# basic_board.net
KiCad netlist of a schematic drawn in EAGLE
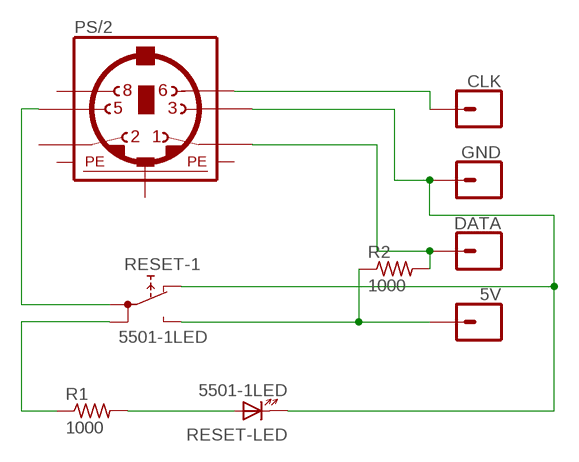
[diagram p0: schematic, sheet 1]

(export (version "E")
  (design (tool "Eeschema 10.0.6"))
  (components
    (comp (ref "5V")
      (value "CONN_01")
      (footprint "eagle-import:1X01")
      (libsource (lib "eagle-import") (part "CONN_01"))
    )
    (comp (ref "CLK")
      (value "CONN_01")
      (footprint "eagle-import:1X01")
      (libsource (lib "eagle-import") (part "CONN_01"))
    )
    (comp (ref "DATA")
      (value "CONN_01")
      (footprint "eagle-import:1X01")
      (libsource (lib "eagle-import") (part "CONN_01"))
    )
    (comp (ref "GND")
      (value "CONN_01")
      (footprint "eagle-import:1X01")
      (libsource (lib "eagle-import") (part "CONN_01"))
    )
    (comp (ref "PS/2")
      (value "MINI_DIN_6")
      (footprint "eagle-import:M_DIN6")
      (libsource (lib "eagle-import") (part "MINI_DIN_6"))
    )
    (comp (ref "R1")
      (value "1000")
      (footprint "eagle-import:0309_12")
      (libsource (lib "eagle-import") (part "R-US_0309/12"))
    )
    (comp (ref "R2")
      (value "1000")
      (footprint "eagle-import:0309_12")
      (libsource (lib "eagle-import") (part "R-US_0309/12"))
    )
    (comp (ref "RESET")
      (value "5501-1LED")
      (footprint "eagle-import:5501-1LED")
      (libsource (lib "eagle-import") (part "55?-1LED01"))
    )
  )
  (nets
    (net (code "1") (name "/PE1") (class "Default")
      (node (ref "PS/2") (pin "SH1") (pinfunction "PE1_SH1") (pintype "power_in"))
    )
    (net (code "2") (name "/PE2") (class "Default")
      (node (ref "PS/2") (pin "SH2") (pinfunction "PE2_SH2") (pintype "power_in"))
    )
    (net (code "3") (name "/PE3") (class "Default")
      (node (ref "PS/2") (pin "SH3") (pinfunction "PE3_SH3") (pintype "power_in"))
    )
    (net (code "4") (name "Net-(5V-Pad1)") (class "Default")
      (node (ref "5V") (pin "1") (pinfunction "1_1") (pintype "passive"))
      (node (ref "R2") (pin "1") (pinfunction "1_1") (pintype "passive"))
      (node (ref "RESET") (pin "NO") (pinfunction "NO_NO") (pintype "passive"))
    )
    (net (code "5") (name "Net-(CLK-Pad1)") (class "Default")
      (node (ref "CLK") (pin "1") (pinfunction "1_1") (pintype "passive"))
      (node (ref "PS/2") (pin "6") (pinfunction "6_6") (pintype "passive"))
    )
    (net (code "6") (name "Net-(DATA-Pad1)") (class "Default")
      (node (ref "DATA") (pin "1") (pinfunction "1_1") (pintype "passive"))
      (node (ref "PS/2") (pin "1") (pinfunction "1_1") (pintype "passive"))
      (node (ref "R2") (pin "2") (pinfunction "2_2") (pintype "passive"))
    )
    (net (code "7") (name "Net-(PS/2-Pad5)") (class "Default")
      (node (ref "PS/2") (pin "5") (pinfunction "5_5") (pintype "passive"))
      (node (ref "RESET") (pin "1A") (pinfunction "1A_1A") (pintype "passive"))
    )
    (net (code "8") (name "Net-(R1-Pad1)") (class "Default")
      (node (ref "R1") (pin "1") (pinfunction "1_1") (pintype "passive"))
      (node (ref "RESET") (pin "1B") (pinfunction "1B_1B") (pintype "passive"))
    )
    (net (code "9") (name "Net-(RESETB-A)") (class "Default")
      (node (ref "R1") (pin "2") (pinfunction "2_2") (pintype "passive"))
      (node (ref "RESET") (pin "+") (pinfunction "A_+") (pintype "passive"))
    )
    (net (code "10") (name "Net-(RESETB-K)") (class "Default")
      (node (ref "GND") (pin "1") (pinfunction "1_1") (pintype "passive"))
      (node (ref "PS/2") (pin "3") (pinfunction "3_3") (pintype "passive"))
      (node (ref "RESET") (pin "-") (pinfunction "K_-") (pintype "passive"))
      (node (ref "RESET") (pin "NC") (pinfunction "NC_NC") (pintype "passive"))
    )
    (net (code "11") (name "unconnected-(PS/2-Pad2)") (class "Default")
      (node (ref "PS/2") (pin "2") (pinfunction "2_2") (pintype "passive"))
    )
    (net (code "12") (name "unconnected-(PS/2-Pad8)") (class "Default")
      (node (ref "PS/2") (pin "8") (pinfunction "8_8") (pintype "passive"))
    )
  )
)
